# 51_24.net
KiCad netlist of a schematic drawn in Altium Designer
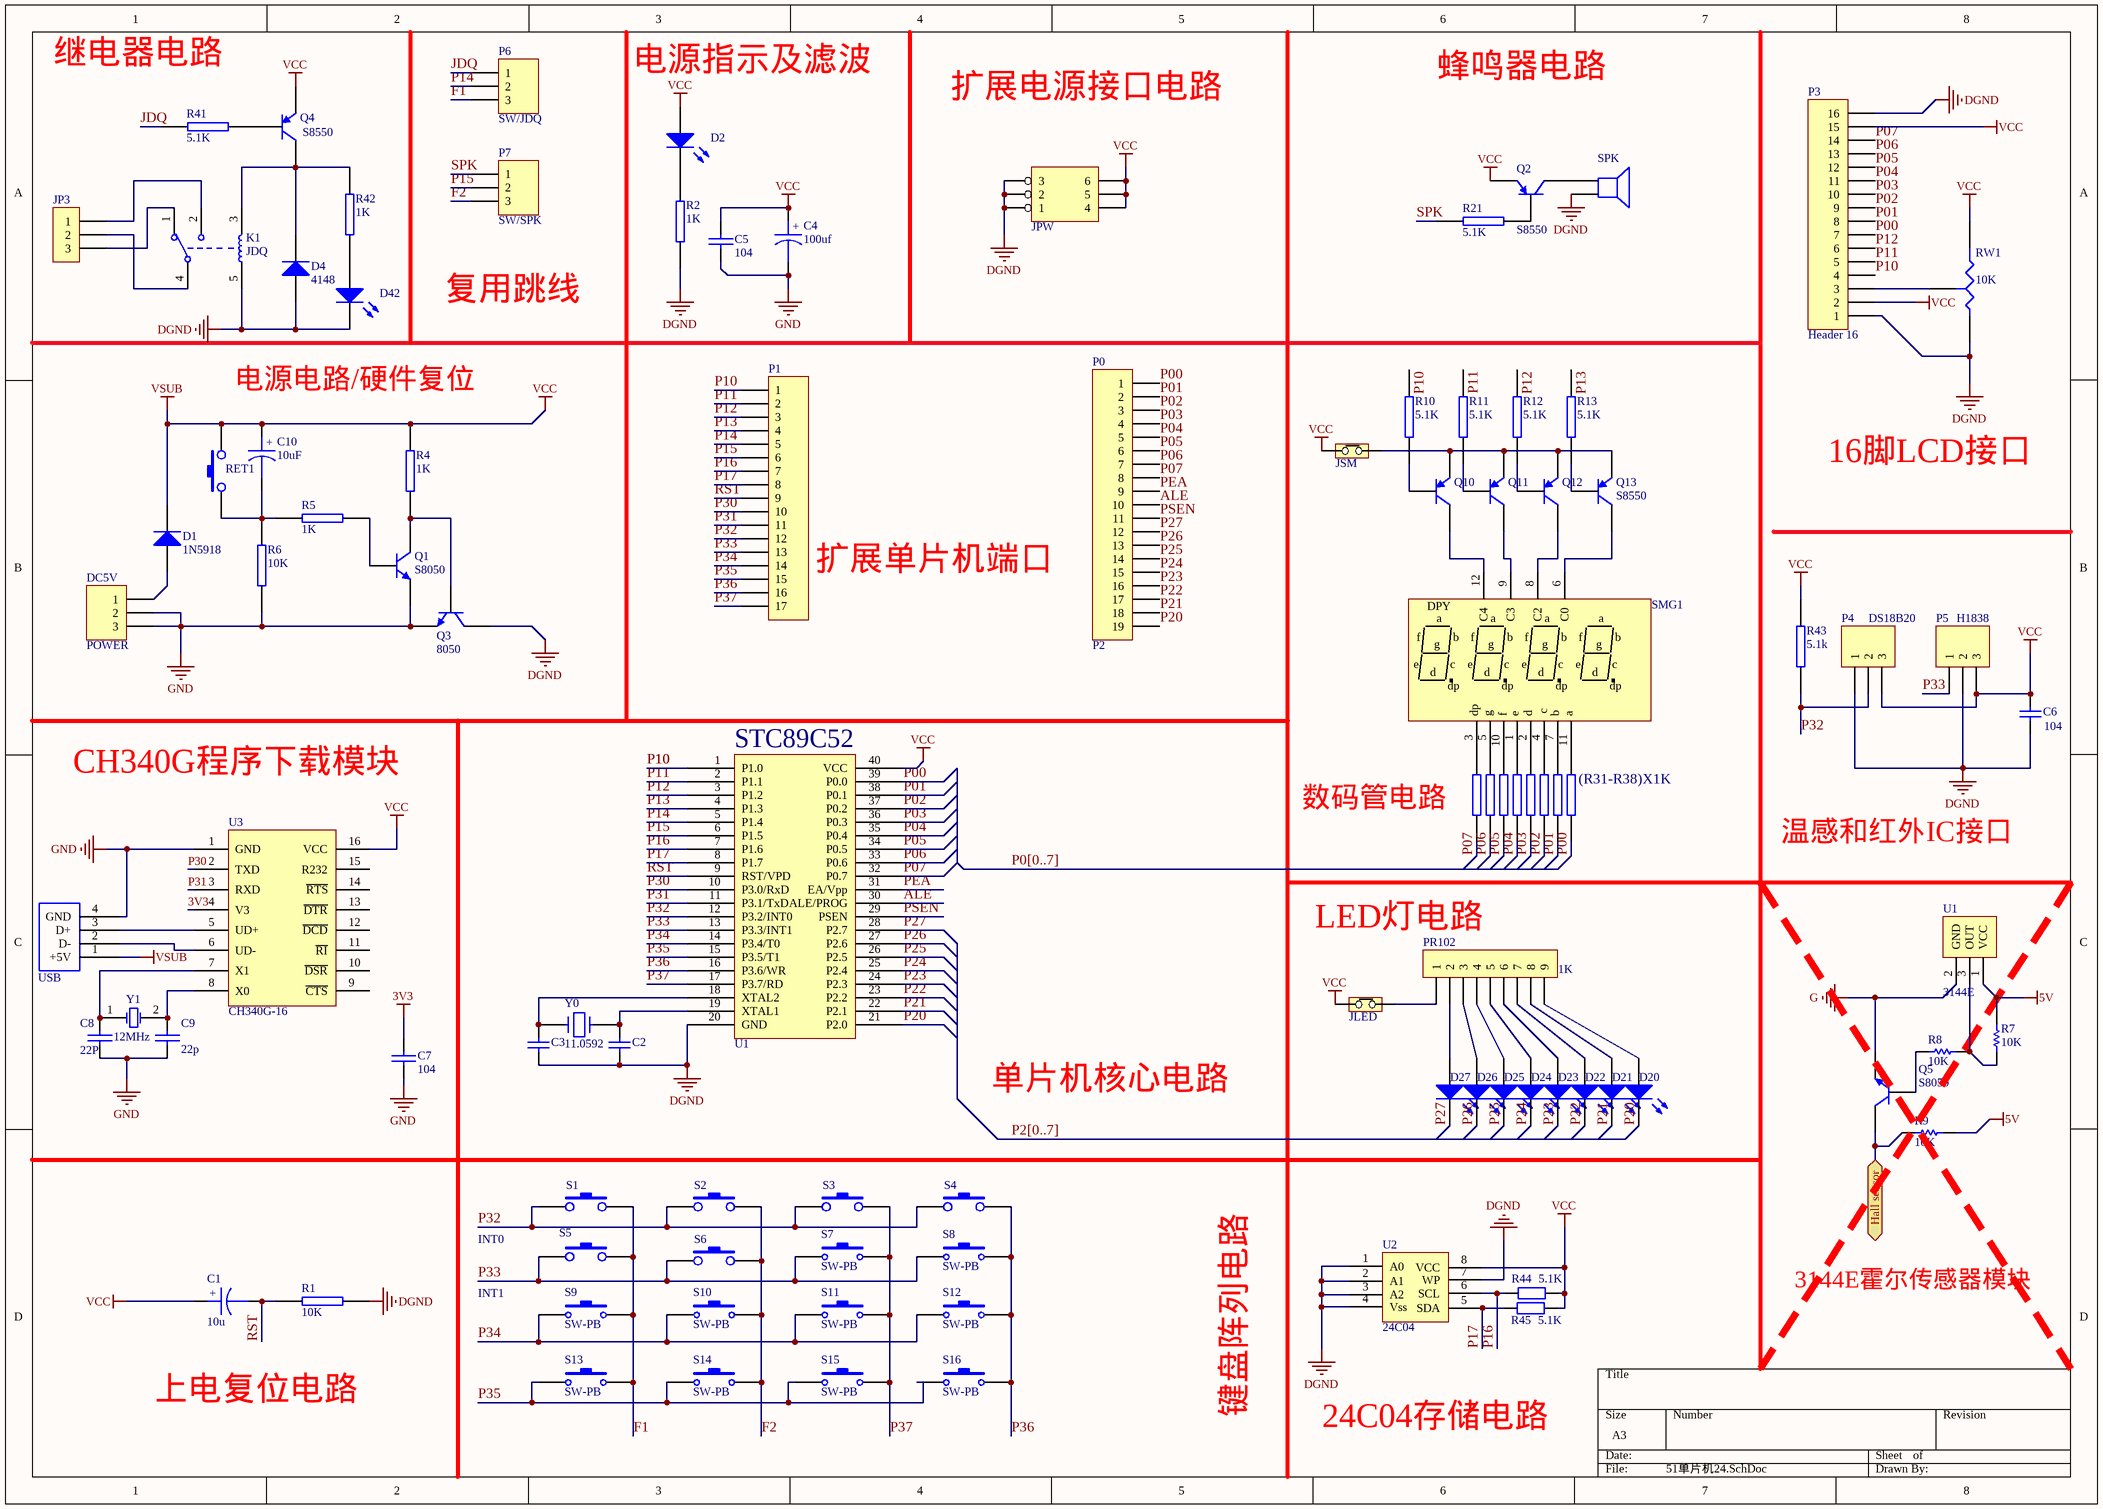
[diagram p0: 51单片机24.SchDoc]

(export (version "E")
  (design (tool "Eeschema 10.0.6"))
  (components
    (comp (ref "C1")
      (value "10u")
      (footprint "C2")
      (description "Capacitor")
      (libsource (lib "1") (part "CAPACITOR POL"))
    )
    (comp (ref "C2")
      (value "Cap")
      (footprint "RAD-0.1")
      (description "Capacitor")
      (fields
        (field (name "MANUFACTURER") "Generic Components")
        (field (name "PUBLISHER") "Altium Hobart Technology Centre")
      )
      (libsource (lib "Miscellaneous Devices") (part "Cap"))
    )
    (comp (ref "C3")
      (value "Cap")
      (footprint "RAD-0.1")
      (description "Capacitor")
      (fields
        (field (name "MANUFACTURER") "Generic Components")
        (field (name "PUBLISHER") "Altium Hobart Technology Centre")
      )
      (libsource (lib "Miscellaneous Devices") (part "Cap"))
    )
    (comp (ref "C4")
      (value "100uf")
      (footprint "c4")
      (description "Capacitor")
      (libsource (lib "1") (part "CAPACITOR POL"))
    )
    (comp (ref "C5")
      (value "104")
      (footprint "RAD-0.1")
      (description "Capacitor")
      (libsource (lib "1") (part "CAP"))
    )
    (comp (ref "C6")
      (value "104")
      (footprint "RAD-0.1")
      (description "Capacitor")
      (fields (field (name "Comment") "Cap") (field (name "PUBLISHER") "Altium Limited"))
      (libsource (lib "Miscellaneous Devices") (part "Cap"))
    )
    (comp (ref "C7")
      (value "104")
      (footprint "RAD-0.1")
      (description "Capacitor")
      (libsource (lib "Miscellaneous Devices") (part "CAP"))
    )
    (comp (ref "C8")
      (value "22P")
      (footprint "RAD-0.1")
      (description "Capacitor")
      (libsource (lib "Miscellaneous Devices") (part "CAP"))
    )
    (comp (ref "C9")
      (value "22p")
      (footprint "RAD-0.1")
      (description "Capacitor")
      (libsource (lib "Miscellaneous Devices") (part "CAP"))
    )
    (comp (ref "C10")
      (value "10uF")
      (footprint "c4")
      (description "Capacitor")
      (libsource (lib "1") (part "CAPACITOR POL"))
    )
    (comp (ref "D1")
      (value "1N5918")
      (footprint "4148")
      (description "3 Amp Medium Power Silicon Rectifier Diode")
      (fields (field (name "PUBLISHER") "Altium Limited"))
      (libsource (lib "Miscellaneous Devices") (part "Diode 1N5408"))
    )
    (comp (ref "D2")
      (value "LED0")
      (footprint "LED2")
      (description "Typical INFRARED GaAs LED")
      (fields (field (name "PUBLISHER") "Altium Limited"))
      (libsource (lib "Miscellaneous Devices") (part "LED0"))
    )
    (comp (ref "D4")
      (value "4148")
      (footprint "DO-41")
      (description "1 Amp General Purpose Rectifier")
      (fields (field (name "PUBLISHER") "Altium Limited"))
      (libsource (lib "Miscellaneous Devices") (part "Diode 1N4001"))
    )
    (comp (ref "D20")
      (value "LED0")
      (footprint "LED8")
      (description "Typical INFRARED GaAs LED")
      (fields (field (name "PUBLISHER") "Altium Limited"))
      (libsource (lib "Miscellaneous Devices") (part "LED0"))
    )
    (comp (ref "D21")
      (value "LED0")
      (footprint "LED8")
      (description "Typical INFRARED GaAs LED")
      (fields (field (name "PUBLISHER") "Altium Limited"))
      (libsource (lib "Miscellaneous Devices") (part "LED0"))
    )
    (comp (ref "D22")
      (value "LED0")
      (footprint "LED8")
      (description "Typical INFRARED GaAs LED")
      (fields (field (name "PUBLISHER") "Altium Limited"))
      (libsource (lib "Miscellaneous Devices") (part "LED0"))
    )
    (comp (ref "D23")
      (value "LED0")
      (footprint "LED8")
      (description "Typical INFRARED GaAs LED")
      (fields (field (name "PUBLISHER") "Altium Limited"))
      (libsource (lib "Miscellaneous Devices") (part "LED0"))
    )
    (comp (ref "D24")
      (value "LED0")
      (footprint "LED8")
      (description "Typical INFRARED GaAs LED")
      (fields (field (name "PUBLISHER") "Altium Limited"))
      (libsource (lib "Miscellaneous Devices") (part "LED0"))
    )
    (comp (ref "D25")
      (value "LED0")
      (footprint "LED8")
      (description "Typical INFRARED GaAs LED")
      (fields (field (name "PUBLISHER") "Altium Limited"))
      (libsource (lib "Miscellaneous Devices") (part "LED0"))
    )
    (comp (ref "D26")
      (value "LED0")
      (footprint "LED8")
      (description "Typical INFRARED GaAs LED")
      (fields (field (name "PUBLISHER") "Altium Limited"))
      (libsource (lib "Miscellaneous Devices") (part "LED0"))
    )
    (comp (ref "D27")
      (value "LED0")
      (footprint "LED8")
      (description "Typical INFRARED GaAs LED")
      (fields (field (name "PUBLISHER") "Altium Limited"))
      (libsource (lib "Miscellaneous Devices") (part "LED0"))
    )
    (comp (ref "D42")
      (value "LED0")
      (footprint "LED2")
      (description "Typical INFRARED GaAs LED")
      (fields (field (name "PUBLISHER") "Altium Limited"))
      (libsource (lib "Miscellaneous Devices") (part "LED0"))
    )
    (comp (ref "DC5V")
      (value "POWER")
      (footprint "DC5V-3")
      (description "Header, 3-Pin")
      (fields (field (name "PUBLISHER") "Altium Limited"))
      (libsource (lib "Miscellaneous Connectors") (part "Header 3"))
    )
    (comp (ref "JLED") (value "JJ") (footprint "j2") (libsource (lib "51单片机24_1") (part "JJ")))
    (comp (ref "JP3") (value "JP3") (footprint "JP3") (libsource (lib "51单片机24") (part "JP3")))
    (comp (ref "JPW") (value "JPW") (footprint "SIP") (libsource (lib "51单片机24_1") (part "JPW")))
    (comp (ref "JSM") (value "JJ") (footprint "j2") (libsource (lib "51单片机24_1") (part "JJ")))
    (comp (ref "K1") (value "JDQ") (footprint "JDQ") (libsource (lib "51单片机24_1") (part "JDQ")))
    (comp (ref "P0")
      (value "P2")
      (footprint "j19")
      (description "Header, 19-Pin")
      (fields (field (name "PUBLISHER") "Altium Limited"))
      (libsource (lib "单片机开发板") (part "Header 19"))
    )
    (comp (ref "P1")
      (value "Header 17")
      (footprint "j17")
      (description "Header, 17-Pin")
      (fields (field (name "PUBLISHER") "Altium Limited"))
      (libsource (lib "单片机开发板") (part "Header 17"))
    )
    (comp (ref "P3")
      (value "Header 16")
      (footprint "HDR1X16")
      (description "Header, 16-Pin")
      (fields (field (name "PUBLISHER") "Altium Limited"))
      (libsource (lib "Miscellaneous Connectors") (part "Header 16"))
    )
    (comp (ref "P4")
      (value "DS18B20")
      (footprint "HDR1X3")
      (description "Header, 3-Pin")
      (fields (field (name "PUBLISHER") "Altium Limited"))
      (libsource (lib "") (part "Header 3_2"))
    )
    (comp (ref "P5")
      (value "H1838")
      (footprint "HDR1X3")
      (description "Header, 3-Pin")
      (fields (field (name "PUBLISHER") "Altium Limited"))
      (libsource (lib "") (part "Header 3_2"))
    )
    (comp (ref "P6")
      (value "SW/JDQ")
      (footprint "HDR1X3")
      (description "Header, 3-Pin")
      (fields (field (name "PUBLISHER") "Altium Limited"))
      (libsource (lib "") (part "Header 3_1"))
    )
    (comp (ref "P7")
      (value "SW/SPK")
      (footprint "HDR1X3")
      (description "Header, 3-Pin")
      (fields (field (name "PUBLISHER") "Altium Limited"))
      (libsource (lib "") (part "Header 3_1"))
    )
    (comp (ref "PR102")
      (value "1K")
      (footprint "SIP-9")
      (description "Connector")
      (libsource (lib "1") (part "CON9"))
    )
    (comp (ref "Q1")
      (value "S8050")
      (footprint "sanjiguan")
      (description "NPN General Purpose Amplifier")
      (fields (field (name "PUBLISHER") "Altium Limited"))
      (libsource (lib "Miscellaneous Devices") (part "2N3904"))
    )
    (comp (ref "Q2")
      (value "S8550")
      (footprint "sanjiguan")
      (description "PNP General Purpose Amplifier")
      (fields (field (name "PUBLISHER") "Altium Limited"))
      (libsource (lib "Miscellaneous Devices") (part "2N3906"))
    )
    (comp (ref "Q3")
      (value "8050")
      (footprint "sanjiguan")
      (description "NPN General Purpose Amplifier")
      (fields (field (name "PUBLISHER") "Altium Limited"))
      (libsource (lib "Miscellaneous Devices") (part "2N3904"))
    )
    (comp (ref "Q4")
      (value "S8550")
      (footprint "sanjiguan")
      (description "PNP General Purpose Amplifier")
      (fields (field (name "PUBLISHER") "Altium Limited"))
      (libsource (lib "Miscellaneous Devices") (part "2N3906"))
    )
    (comp (ref "Q5")
      (value "S8050")
      (footprint "sanjiguan")
      (description "NPN General Purpose Amplifier")
      (fields (field (name "PUBLISHER") "Altium Limited"))
      (libsource (lib "Miscellaneous Devices") (part "2N3904"))
    )
    (comp (ref "Q10")
      (value "S8550")
      (footprint "sanjiguan")
      (description "PNP General Purpose Amplifier")
      (fields (field (name "PUBLISHER") "Altium Limited"))
      (libsource (lib "Miscellaneous Devices") (part "2N3906"))
    )
    (comp (ref "Q11")
      (value "S8550")
      (footprint "sanjiguan")
      (description "PNP General Purpose Amplifier")
      (fields (field (name "PUBLISHER") "Altium Limited"))
      (libsource (lib "Miscellaneous Devices") (part "2N3906"))
    )
    (comp (ref "Q12")
      (value "S8550")
      (footprint "sanjiguan")
      (description "PNP General Purpose Amplifier")
      (fields (field (name "PUBLISHER") "Altium Limited"))
      (libsource (lib "Miscellaneous Devices") (part "2N3906"))
    )
    (comp (ref "Q13")
      (value "S8550")
      (footprint "sanjiguan")
      (description "PNP General Purpose Amplifier")
      (fields (field (name "PUBLISHER") "Altium Limited"))
      (libsource (lib "Miscellaneous Devices") (part "2N3906"))
    )
    (comp (ref "R1")
      (value "10K")
      (footprint "axial0.4")
      (libsource (lib "Miscellaneous Devices") (part "RES2"))
    )
    (comp (ref "R2") (value "1K") (footprint "axial0.4") (libsource (lib "1") (part "RES2")))
    (comp (ref "R4")
      (value "1K")
      (footprint "axial0.4")
      (libsource (lib "Miscellaneous Devices") (part "RES2"))
    )
    (comp (ref "R5")
      (value "1K")
      (footprint "axial0.4")
      (libsource (lib "Miscellaneous Devices") (part "RES2"))
    )
    (comp (ref "R6")
      (value "10K")
      (footprint "axial0.4")
      (libsource (lib "Miscellaneous Devices") (part "RES2"))
    )
    (comp (ref "R7")
      (value "10K")
      (footprint "AXIAL-0.3")
      (description "Resistor")
      (fields (field (name "Comment") "Res1") (field (name "PUBLISHER") "Altium Limited"))
      (libsource (lib "Miscellaneous Devices") (part "Res1"))
    )
    (comp (ref "R8")
      (value "10K")
      (footprint "AXIAL-0.3")
      (description "Resistor")
      (fields (field (name "Comment") "Res1") (field (name "PUBLISHER") "Altium Limited"))
      (libsource (lib "Miscellaneous Devices") (part "Res1"))
    )
    (comp (ref "R9")
      (value "10K")
      (footprint "AXIAL-0.3")
      (description "Resistor")
      (fields (field (name "Comment") "Res1") (field (name "PUBLISHER") "Altium Limited"))
      (libsource (lib "Miscellaneous Devices") (part "Res1"))
    )
    (comp (ref "R10")
      (value "5.1K")
      (footprint "axial0.4")
      (libsource (lib "Miscellaneous Devices") (part "RES2"))
    )
    (comp (ref "R11")
      (value "5.1K")
      (footprint "axial0.4")
      (libsource (lib "Miscellaneous Devices") (part "RES2"))
    )
    (comp (ref "R12")
      (value "5.1K")
      (footprint "axial0.4")
      (libsource (lib "Miscellaneous Devices") (part "RES2"))
    )
    (comp (ref "R13")
      (value "5.1K")
      (footprint "axial0.4")
      (libsource (lib "Miscellaneous Devices") (part "RES2"))
    )
    (comp (ref "R21")
      (value "5.1K")
      (footprint "axial0.4")
      (libsource (lib "Miscellaneous Devices") (part "RES2"))
    )
    (comp (ref "R31")
      (value "1K")
      (footprint "axial0.4")
      (libsource (lib "Miscellaneous Devices") (part "RES2"))
    )
    (comp (ref "R32")
      (value "1K")
      (footprint "axial0.4")
      (libsource (lib "Miscellaneous Devices") (part "RES2"))
    )
    (comp (ref "R33")
      (value "1K")
      (footprint "axial0.4")
      (libsource (lib "Miscellaneous Devices") (part "RES2"))
    )
    (comp (ref "R34")
      (value "1K")
      (footprint "axial0.4")
      (libsource (lib "Miscellaneous Devices") (part "RES2"))
    )
    (comp (ref "R35")
      (value "1K")
      (footprint "axial0.4")
      (libsource (lib "Miscellaneous Devices") (part "RES2"))
    )
    (comp (ref "R36")
      (value "1K")
      (footprint "axial0.4")
      (libsource (lib "Miscellaneous Devices") (part "RES2"))
    )
    (comp (ref "R37")
      (value "1K")
      (footprint "axial0.4")
      (libsource (lib "Miscellaneous Devices") (part "RES2"))
    )
    (comp (ref "R38")
      (value "1K")
      (footprint "axial0.4")
      (libsource (lib "Miscellaneous Devices") (part "RES2"))
    )
    (comp (ref "R41")
      (value "5.1K")
      (footprint "axial0.4")
      (libsource (lib "Miscellaneous Devices") (part "RES2"))
    )
    (comp (ref "R42")
      (value "1K")
      (footprint "axial0.4")
      (libsource (lib "Miscellaneous Devices") (part "RES2"))
    )
    (comp (ref "R43")
      (value "5.1k")
      (footprint "axial0.4")
      (libsource (lib "Miscellaneous Devices") (part "RES2"))
    )
    (comp (ref "R44")
      (value "5.1K")
      (footprint "AXIAL-0.4")
      (description "Resistor")
      (fields (field (name "PUBLISHER") "Altium Limited"))
      (libsource (lib "Miscellaneous Devices") (part "Res2"))
    )
    (comp (ref "R45")
      (value "5.1K")
      (footprint "AXIAL-0.4")
      (description "Resistor")
      (fields (field (name "PUBLISHER") "Altium Limited"))
      (libsource (lib "Miscellaneous Devices") (part "Res2"))
    )
    (comp (ref "RET1")
      (value "RET")
      (footprint "sw")
      (libsource (lib "Miscellaneous Devices") (part "SW-PB"))
    )
    (comp (ref "RW1")
      (value "10K")
      (footprint "RW")
      (description "Tapped Resistor")
      (fields (field (name "Comment") "Res Tap") (field (name "PUBLISHER") "Altium Limited"))
      (libsource (lib "Miscellaneous Devices") (part "Res Tap"))
    )
    (comp (ref "S1") (value "RET") (footprint "sw") (libsource (lib "Miscellaneous Devices") (part "SW-PB")))
    (comp (ref "S2") (value "RET") (footprint "sw") (libsource (lib "Miscellaneous Devices") (part "SW-PB")))
    (comp (ref "S3") (value "RET") (footprint "sw") (libsource (lib "Miscellaneous Devices") (part "SW-PB")))
    (comp (ref "S4") (value "RET") (footprint "sw") (libsource (lib "Miscellaneous Devices") (part "SW-PB")))
    (comp (ref "S5") (value "RET") (footprint "sw") (libsource (lib "Miscellaneous Devices") (part "SW-PB")))
    (comp (ref "S6") (value "RET") (footprint "sw") (libsource (lib "Miscellaneous Devices") (part "SW-PB")))
    (comp (ref "S7")
      (value "SW-PB")
      (footprint "SW")
      (description "Switch")
      (fields (field (name "PUBLISHER") "Altium Limited"))
      (libsource (lib "") (part "SW-PB_1"))
    )
    (comp (ref "S8")
      (value "SW-PB")
      (footprint "SW")
      (description "Switch")
      (fields (field (name "PUBLISHER") "Altium Limited"))
      (libsource (lib "") (part "SW-PB_1"))
    )
    (comp (ref "S9")
      (value "SW-PB")
      (footprint "SW")
      (description "Switch")
      (fields (field (name "PUBLISHER") "Altium Limited"))
      (libsource (lib "") (part "SW-PB_1"))
    )
    (comp (ref "S10")
      (value "SW-PB")
      (footprint "SW")
      (description "Switch")
      (fields (field (name "PUBLISHER") "Altium Limited"))
      (libsource (lib "") (part "SW-PB_1"))
    )
    (comp (ref "S11")
      (value "SW-PB")
      (footprint "SW")
      (description "Switch")
      (fields (field (name "PUBLISHER") "Altium Limited"))
      (libsource (lib "") (part "SW-PB_1"))
    )
    (comp (ref "S12")
      (value "SW-PB")
      (footprint "SW")
      (description "Switch")
      (fields (field (name "PUBLISHER") "Altium Limited"))
      (libsource (lib "") (part "SW-PB_1"))
    )
    (comp (ref "S13")
      (value "SW-PB")
      (footprint "SW")
      (description "Switch")
      (fields (field (name "PUBLISHER") "Altium Limited"))
      (libsource (lib "") (part "SW-PB_1"))
    )
    (comp (ref "S14")
      (value "SW-PB")
      (footprint "SW")
      (description "Switch")
      (fields (field (name "PUBLISHER") "Altium Limited"))
      (libsource (lib "") (part "SW-PB_1"))
    )
    (comp (ref "S15")
      (value "SW-PB")
      (footprint "SW")
      (description "Switch")
      (fields (field (name "PUBLISHER") "Altium Limited"))
      (libsource (lib "") (part "SW-PB_1"))
    )
    (comp (ref "S16")
      (value "SW-PB")
      (footprint "SW")
      (description "Switch")
      (fields (field (name "PUBLISHER") "Altium Limited"))
      (libsource (lib "") (part "SW-PB_1"))
    )
    (comp (ref "SMG1") (value "SMG") (footprint "smg") (libsource (lib "51单片机24") (part "SMG")))
    (comp (ref "SPK")
      (value "Speaker")
      (footprint "HDR1X4")
      (libsource (lib "Miscellaneous Devices") (part "SPEAKER"))
    )
    (comp (ref "STC89C52") (value "U1") (footprint "S52") (libsource (lib "51单片机24_1") (part "89C51")))
    (comp (ref "U1")
      (value "3144E")
      (footprint "HDR1X3")
      (description "开关式霍尔传感器")
      (libsource (lib "PCB-Design-of-the-8051") (part "3144E"))
    )
    (comp (ref "U2") (value "24C04") (footprint "DIP8") (libsource (lib "51单片机24_1") (part "24C04")))
    (comp (ref "U3")
      (value "CH340G-16")
      (footprint "SOP-16 - duplicate")
      (libsource (lib "51单片机24_1") (part "CH340G-16"))
    )
    (comp (ref "USB")
      (value "CON4")
      (footprint "USB")
      (description "Connector")
      (libsource (lib "1") (part "CON4"))
    )
    (comp (ref "Y0")
      (value "11.0592")
      (footprint "XTAL1")
      (description "Crystal")
      (libsource (lib "1") (part "CRYSTAL"))
    )
    (comp (ref "Y1")
      (value "12MHz")
      (footprint "XTAL1")
      (description "Crystal Oscillator")
      (fields (field (name "PUBLISHER") "Altium Limited"))
      (libsource (lib "Miscellaneous Devices") (part "XTAL"))
    )
  )
  (nets
    (net (code "1") (name "/ALE") (class "Default")
      (node (ref "P0") (pin "10") (pinfunction "10_10") (pintype "passive"))
      (node (ref "STC89C52") (pin "30") (pinfunction "ALE/PROG_30") (pintype "passive"))
    )
    (net (code "2") (name "/F1") (class "Default")
      (node (ref "P6") (pin "3") (pinfunction "3_3") (pintype "passive"))
      (node (ref "S1") (pin "2") (pinfunction "2_2") (pintype "passive"))
      (node (ref "S13") (pin "2") (pinfunction "2_2") (pintype "passive"))
      (node (ref "S5") (pin "2") (pinfunction "2_2") (pintype "passive"))
      (node (ref "S9") (pin "2") (pinfunction "2_2") (pintype "passive"))
    )
    (net (code "3") (name "/F2") (class "Default")
      (node (ref "P7") (pin "3") (pinfunction "3_3") (pintype "passive"))
      (node (ref "S10") (pin "2") (pinfunction "2_2") (pintype "passive"))
      (node (ref "S14") (pin "2") (pinfunction "2_2") (pintype "passive"))
      (node (ref "S2") (pin "2") (pinfunction "2_2") (pintype "passive"))
      (node (ref "S6") (pin "2") (pinfunction "2_2") (pintype "passive"))
    )
    (net (code "4") (name "/Hall sensor") (class "Default")
      (node (ref "Q5") (pin "3") (pinfunction "C_3") (pintype "passive"))
      (node (ref "R9") (pin "1") (pinfunction "1_1") (pintype "passive"))
    )
    (net (code "5") (name "/JDQ") (class "Default")
      (node (ref "P6") (pin "1") (pinfunction "1_1") (pintype "passive"))
      (node (ref "R41") (pin "1") (pinfunction "1_1") (pintype "passive"))
    )
    (net (code "6") (name "/P00") (class "Default")
      (node (ref "P0") (pin "1") (pinfunction "1_1") (pintype "passive"))
      (node (ref "P3") (pin "7") (pinfunction "7_7") (pintype "passive"))
      (node (ref "R31") (pin "1") (pinfunction "1_1") (pintype "passive"))
      (node (ref "STC89C52") (pin "39") (pinfunction "P0.0_39") (pintype "passive"))
    )
    (net (code "8") (name "/P01") (class "Default")
      (node (ref "P0") (pin "2") (pinfunction "2_2") (pintype "passive"))
      (node (ref "P3") (pin "8") (pinfunction "8_8") (pintype "passive"))
      (node (ref "R32") (pin "1") (pinfunction "1_1") (pintype "passive"))
      (node (ref "STC89C52") (pin "38") (pinfunction "P0.1_38") (pintype "passive"))
    )
    (net (code "9") (name "/P02") (class "Default")
      (node (ref "P0") (pin "3") (pinfunction "3_3") (pintype "passive"))
      (node (ref "P3") (pin "9") (pinfunction "9_9") (pintype "passive"))
      (node (ref "R33") (pin "1") (pinfunction "1_1") (pintype "passive"))
      (node (ref "STC89C52") (pin "37") (pinfunction "P0.2_37") (pintype "passive"))
    )
    (net (code "11") (name "/P03") (class "Default")
      (node (ref "P0") (pin "4") (pinfunction "4_4") (pintype "passive"))
      (node (ref "P3") (pin "10") (pinfunction "10_10") (pintype "passive"))
      (node (ref "R34") (pin "1") (pinfunction "1_1") (pintype "passive"))
      (node (ref "STC89C52") (pin "36") (pinfunction "P0.3_36") (pintype "passive"))
    )
    (net (code "12") (name "/P04") (class "Default")
      (node (ref "P0") (pin "5") (pinfunction "5_5") (pintype "passive"))
      (node (ref "P3") (pin "11") (pinfunction "11_11") (pintype "passive"))
      (node (ref "R35") (pin "1") (pinfunction "1_1") (pintype "passive"))
      (node (ref "STC89C52") (pin "35") (pinfunction "P0.4_35") (pintype "passive"))
    )
    (net (code "13") (name "/P05") (class "Default")
      (node (ref "P0") (pin "6") (pinfunction "6_6") (pintype "passive"))
      (node (ref "P3") (pin "12") (pinfunction "12_12") (pintype "passive"))
      (node (ref "R36") (pin "1") (pinfunction "1_1") (pintype "passive"))
      (node (ref "STC89C52") (pin "34") (pinfunction "P0.5_34") (pintype "passive"))
    )
    (net (code "14") (name "/P06") (class "Default")
      (node (ref "P0") (pin "7") (pinfunction "7_7") (pintype "passive"))
      (node (ref "P3") (pin "13") (pinfunction "13_13") (pintype "passive"))
      (node (ref "R37") (pin "1") (pinfunction "1_1") (pintype "passive"))
      (node (ref "STC89C52") (pin "33") (pinfunction "P0.6_33") (pintype "passive"))
    )
    (net (code "15") (name "/P07") (class "Default")
      (node (ref "P0") (pin "8") (pinfunction "8_8") (pintype "passive"))
      (node (ref "P3") (pin "14") (pinfunction "14_14") (pintype "passive"))
      (node (ref "R38") (pin "1") (pinfunction "1_1") (pintype "passive"))
      (node (ref "STC89C52") (pin "32") (pinfunction "P0.7_32") (pintype "passive"))
    )
    (net (code "16") (name "/P10") (class "Default")
      (node (ref "P1") (pin "1") (pinfunction "1_1") (pintype "passive"))
      (node (ref "P3") (pin "4") (pinfunction "4_4") (pintype "passive"))
      (node (ref "R10") (pin "2") (pinfunction "2_2") (pintype "passive"))
      (node (ref "STC89C52") (pin "1") (pinfunction "P1.0_1") (pintype "passive"))
    )
    (net (code "17") (name "/P11") (class "Default")
      (node (ref "P1") (pin "2") (pinfunction "2_2") (pintype "passive"))
      (node (ref "P3") (pin "5") (pinfunction "5_5") (pintype "passive"))
      (node (ref "R11") (pin "2") (pinfunction "2_2") (pintype "passive"))
      (node (ref "STC89C52") (pin "2") (pinfunction "P1.1_2") (pintype "passive"))
    )
    (net (code "18") (name "/P12") (class "Default")
      (node (ref "P1") (pin "3") (pinfunction "3_3") (pintype "passive"))
      (node (ref "P3") (pin "6") (pinfunction "6_6") (pintype "passive"))
      (node (ref "R12") (pin "2") (pinfunction "2_2") (pintype "passive"))
      (node (ref "STC89C52") (pin "3") (pinfunction "P1.2_3") (pintype "passive"))
    )
    (net (code "19") (name "/P13") (class "Default")
      (node (ref "P1") (pin "4") (pinfunction "4_4") (pintype "passive"))
      (node (ref "R13") (pin "2") (pinfunction "2_2") (pintype "passive"))
      (node (ref "STC89C52") (pin "4") (pinfunction "P1.3_4") (pintype "passive"))
    )
    (net (code "20") (name "/P14") (class "Default")
      (node (ref "P1") (pin "5") (pinfunction "5_5") (pintype "passive"))
      (node (ref "P6") (pin "2") (pinfunction "2_2") (pintype "passive"))
      (node (ref "STC89C52") (pin "5") (pinfunction "P1.4_5") (pintype "passive"))
    )
    (net (code "21") (name "/P15") (class "Default")
      (node (ref "P1") (pin "6") (pinfunction "6_6") (pintype "passive"))
      (node (ref "P7") (pin "2") (pinfunction "2_2") (pintype "passive"))
      (node (ref "STC89C52") (pin "6") (pinfunction "P1.5_6") (pintype "passive"))
    )
    (net (code "22") (name "/P16") (class "Default")
      (node (ref "P1") (pin "7") (pinfunction "7_7") (pintype "passive"))
      (node (ref "R44") (pin "1") (pinfunction "1_1") (pintype "passive"))
      (node (ref "STC89C52") (pin "7") (pinfunction "P1.6_7") (pintype "passive"))
      (node (ref "U2") (pin "6") (pinfunction "SCL_6") (pintype "passive"))
    )
    (net (code "23") (name "/P17") (class "Default")
      (node (ref "P1") (pin "8") (pinfunction "8_8") (pintype "passive"))
      (node (ref "R45") (pin "1") (pinfunction "1_1") (pintype "passive"))
      (node (ref "STC89C52") (pin "8") (pinfunction "P1.7_8") (pintype "passive"))
      (node (ref "U2") (pin "5") (pinfunction "SDA_5") (pintype "passive"))
    )
    (net (code "24") (name "/P20") (class "Default")
      (node (ref "D20") (pin "2") (pinfunction "K_2") (pintype "passive"))
      (node (ref "P0") (pin "19") (pinfunction "19_19") (pintype "passive"))
      (node (ref "STC89C52") (pin "21") (pinfunction "P2.0_21") (pintype "passive"))
    )
    (net (code "25") (name "/P21") (class "Default")
      (node (ref "D21") (pin "2") (pinfunction "K_2") (pintype "passive"))
      (node (ref "P0") (pin "18") (pinfunction "18_18") (pintype "passive"))
      (node (ref "STC89C52") (pin "22") (pinfunction "P2.1_22") (pintype "passive"))
    )
    (net (code "26") (name "/P22") (class "Default")
      (node (ref "D22") (pin "2") (pinfunction "K_2") (pintype "passive"))
      (node (ref "P0") (pin "17") (pinfunction "17_17") (pintype "passive"))
      (node (ref "STC89C52") (pin "23") (pinfunction "P2.2_23") (pintype "passive"))
    )
    (net (code "27") (name "/P23") (class "Default")
      (node (ref "D23") (pin "2") (pinfunction "K_2") (pintype "passive"))
      (node (ref "P0") (pin "16") (pinfunction "16_16") (pintype "passive"))
      (node (ref "STC89C52") (pin "24") (pinfunction "P2.3_24") (pintype "passive"))
    )
    (net (code "28") (name "/P24") (class "Default")
      (node (ref "D24") (pin "2") (pinfunction "K_2") (pintype "passive"))
      (node (ref "P0") (pin "15") (pinfunction "15_15") (pintype "passive"))
      (node (ref "STC89C52") (pin "25") (pinfunction "P2.4_25") (pintype "passive"))
    )
    (net (code "29") (name "/P25") (class "Default")
      (node (ref "D25") (pin "2") (pinfunction "K_2") (pintype "passive"))
      (node (ref "P0") (pin "14") (pinfunction "14_14") (pintype "passive"))
      (node (ref "STC89C52") (pin "26") (pinfunction "P2.5_26") (pintype "passive"))
    )
    (net (code "30") (name "/P26") (class "Default")
      (node (ref "D26") (pin "2") (pinfunction "K_2") (pintype "passive"))
      (node (ref "P0") (pin "13") (pinfunction "13_13") (pintype "passive"))
      (node (ref "STC89C52") (pin "27") (pinfunction "P2.6_27") (pintype "passive"))
    )
    (net (code "31") (name "/P27") (class "Default")
      (node (ref "D27") (pin "2") (pinfunction "K_2") (pintype "passive"))
      (node (ref "P0") (pin "12") (pinfunction "12_12") (pintype "passive"))
      (node (ref "STC89C52") (pin "28") (pinfunction "P2.7_28") (pintype "passive"))
    )
    (net (code "32") (name "/P30") (class "Default")
      (node (ref "P1") (pin "10") (pinfunction "10_10") (pintype "passive"))
      (node (ref "STC89C52") (pin "10") (pinfunction "P3.0/RxD_10") (pintype "passive"))
      (node (ref "U3") (pin "2") (pinfunction "TXD_2") (pintype "passive"))
    )
    (net (code "33") (name "/P31") (class "Default")
      (node (ref "P1") (pin "11") (pinfunction "11_11") (pintype "passive"))
      (node (ref "STC89C52") (pin "11") (pinfunction "P3.1/TxD_11") (pintype "passive"))
      (node (ref "U3") (pin "3") (pinfunction "RXD_3") (pintype "passive"))
    )
    (net (code "34") (name "/P32") (class "Default")
      (node (ref "P1") (pin "12") (pinfunction "12_12") (pintype "passive"))
      (node (ref "P4") (pin "2") (pinfunction "2_2") (pintype "passive"))
      (node (ref "R43") (pin "1") (pinfunction "1_1") (pintype "passive"))
      (node (ref "S1") (pin "1") (pinfunction "1_1") (pintype "passive"))
      (node (ref "S2") (pin "1") (pinfunction "1_1") (pintype "passive"))
      (node (ref "S3") (pin "1") (pinfunction "1_1") (pintype "passive"))
      (node (ref "S4") (pin "1") (pinfunction "1_1") (pintype "passive"))
      (node (ref "STC89C52") (pin "12") (pinfunction "P3.2/INT0_12") (pintype "passive"))
    )
    (net (code "35") (name "/P33") (class "Default")
      (node (ref "P1") (pin "13") (pinfunction "13_13") (pintype "passive"))
      (node (ref "P5") (pin "1") (pinfunction "1_1") (pintype "passive"))
      (node (ref "S5") (pin "1") (pinfunction "1_1") (pintype "passive"))
      (node (ref "S6") (pin "1") (pinfunction "1_1") (pintype "passive"))
      (node (ref "S7") (pin "1") (pinfunction "1_1") (pintype "passive"))
      (node (ref "S8") (pin "1") (pinfunction "1_1") (pintype "passive"))
      (node (ref "STC89C52") (pin "13") (pinfunction "P3.3/INT1_13") (pintype "passive"))
    )
    (net (code "36") (name "/P34") (class "Default")
      (node (ref "P1") (pin "14") (pinfunction "14_14") (pintype "passive"))
      (node (ref "S10") (pin "1") (pinfunction "1_1") (pintype "passive"))
      (node (ref "S11") (pin "1") (pinfunction "1_1") (pintype "passive"))
      (node (ref "S12") (pin "1") (pinfunction "1_1") (pintype "passive"))
      (node (ref "S9") (pin "1") (pinfunction "1_1") (pintype "passive"))
      (node (ref "STC89C52") (pin "14") (pinfunction "P3.4/T0_14") (pintype "passive"))
    )
    (net (code "37") (name "/P35") (class "Default")
      (node (ref "P1") (pin "15") (pinfunction "15_15") (pintype "passive"))
      (node (ref "S13") (pin "1") (pinfunction "1_1") (pintype "passive"))
      (node (ref "S14") (pin "1") (pinfunction "1_1") (pintype "passive"))
      (node (ref "S15") (pin "1") (pinfunction "1_1") (pintype "passive"))
      (node (ref "S16") (pin "1") (pinfunction "1_1") (pintype "passive"))
      (node (ref "STC89C52") (pin "15") (pinfunction "P3.5/T1_15") (pintype "passive"))
    )
    (net (code "38") (name "/P36") (class "Default")
      (node (ref "P1") (pin "16") (pinfunction "16_16") (pintype "passive"))
      (node (ref "S12") (pin "2") (pinfunction "2_2") (pintype "passive"))
      (node (ref "S16") (pin "2") (pinfunction "2_2") (pintype "passive"))
      (node (ref "S4") (pin "2") (pinfunction "2_2") (pintype "passive"))
      (node (ref "S8") (pin "2") (pinfunction "2_2") (pintype "passive"))
      (node (ref "STC89C52") (pin "16") (pinfunction "P3.6/WR_16") (pintype "passive"))
    )
    (net (code "39") (name "/P37") (class "Default")
      (node (ref "P1") (pin "17") (pinfunction "17_17") (pintype "passive"))
      (node (ref "S11") (pin "2") (pinfunction "2_2") (pintype "passive"))
      (node (ref "S15") (pin "2") (pinfunction "2_2") (pintype "passive"))
      (node (ref "S3") (pin "2") (pinfunction "2_2") (pintype "passive"))
      (node (ref "S7") (pin "2") (pinfunction "2_2") (pintype "passive"))
      (node (ref "STC89C52") (pin "17") (pinfunction "P3.7/RD_17") (pintype "passive"))
    )
    (net (code "40") (name "/PEA") (class "Default")
      (node (ref "P0") (pin "9") (pinfunction "9_9") (pintype "passive"))
      (node (ref "STC89C52") (pin "31") (pinfunction "EA/Vpp_31") (pintype "passive"))
    )
    (net (code "41") (name "/PSEN") (class "Default")
      (node (ref "P0") (pin "11") (pinfunction "11_11") (pintype "passive"))
      (node (ref "STC89C52") (pin "29") (pinfunction "PSEN_29") (pintype "passive"))
    )
    (net (code "42") (name "/RST") (class "Default")
      (node (ref "C1") (pin "2") (pinfunction "2_2") (pintype "passive"))
      (node (ref "P1") (pin "9") (pinfunction "9_9") (pintype "passive"))
      (node (ref "R1") (pin "2") (pinfunction "2_2") (pintype "passive"))
      (node (ref "STC89C52") (pin "9") (pinfunction "RST/VPD_9") (pintype "passive"))
    )
    (net (code "43") (name "/SPK") (class "Default")
      (node (ref "P7") (pin "1") (pinfunction "1_1") (pintype "passive"))
      (node (ref "R21") (pin "1") (pinfunction "1_1") (pintype "passive"))
    )
    (net (code "44") (name "3V3") (class "Default")
      (node (ref "C7") (pin "1") (pinfunction "1_1") (pintype "passive"))
      (node (ref "U3") (pin "4") (pinfunction "V3_4") (pintype "passive"))
    )
    (net (code "45") (name "5V") (class "Default")
      (node (ref "R7") (pin "2") (pinfunction "2_2") (pintype "passive"))
      (node (ref "R9") (pin "2") (pinfunction "2_2") (pintype "passive"))
      (node (ref "U1") (pin "1") (pinfunction "VCC_1") (pintype "passive"))
    )
    (net (code "46") (name "DGND") (class "Default")
      (node (ref "C2") (pin "1") (pinfunction "1_1") (pintype "passive"))
      (node (ref "C3") (pin "1") (pinfunction "1_1") (pintype "passive"))
      (node (ref "C6") (pin "1") (pinfunction "1_1") (pintype "passive"))
      (node (ref "D4") (pin "1") (pinfunction "A_1") (pintype "passive"))
      (node (ref "D42") (pin "2") (pinfunction "K_2") (pintype "passive"))
      (node (ref "JPW") (pin "1") (pinfunction "1_1") (pintype "passive"))
      (node (ref "JPW") (pin "2") (pinfunction "2_2") (pintype "passive"))
      (node (ref "JPW") (pin "3") (pinfunction "3_3") (pintype "passive"))
      (node (ref "K1") (pin "5") (pinfunction "5_5") (pintype "passive"))
      (node (ref "P3") (pin "1") (pinfunction "1_1") (pintype "passive"))
      (node (ref "P3") (pin "16") (pinfunction "16_16") (pintype "passive"))
      (node (ref "P4") (pin "1") (pinfunction "1_1") (pintype "passive"))
      (node (ref "P5") (pin "2") (pinfunction "2_2") (pintype "passive"))
      (node (ref "Q3") (pin "3") (pinfunction "C_3") (pintype "passive"))
      (node (ref "R1") (pin "1") (pinfunction "1_1") (pintype "passive"))
      (node (ref "R2") (pin "1") (pinfunction "1_1") (pintype "passive"))
      (node (ref "RW1") (pin "1") (pinfunction "A_1") (pintype "passive"))
      (node (ref "SPK") (pin "2") (pinfunction "K_2") (pintype "passive"))
      (node (ref "STC89C52") (pin "20") (pinfunction "GND_20") (pintype "passive"))
      (node (ref "U2") (pin "1") (pinfunction "A0_1") (pintype "passive"))
      (node (ref "U2") (pin "2") (pinfunction "A1_2") (pintype "passive"))
      (node (ref "U2") (pin "3") (pinfunction "A2_3") (pintype "passive"))
      (node (ref "U2") (pin "4") (pinfunction "Vss_4") (pintype "passive"))
      (node (ref "U2") (pin "7") (pinfunction "WP_7") (pintype "passive"))
    )
    (net (code "47") (name "G") (class "Default")
      (node (ref "Q5") (pin "1") (pinfunction "E_1") (pintype "passive"))
      (node (ref "U1") (pin "2") (pinfunction "GND_2") (pintype "passive"))
    )
    (net (code "48") (name "GND") (class "Default")
      (node (ref "C4") (pin "2") (pinfunction "2_2") (pintype "passive"))
      (node (ref "C5") (pin "2") (pinfunction "2_2") (pintype "passive"))
      (node (ref "C7") (pin "2") (pinfunction "2_2") (pintype "passive"))
      (node (ref "C8") (pin "2") (pinfunction "2_2") (pintype "passive"))
      (node (ref "C9") (pin "2") (pinfunction "2_2") (pintype "passive"))
      (node (ref "DC5V") (pin "2") (pinfunction "2_2") (pintype "passive"))
      (node (ref "DC5V") (pin "3") (pinfunction "3_3") (pintype "passive"))
      (node (ref "Q1") (pin "1") (pinfunction "E_1") (pintype "passive"))
      (node (ref "Q3") (pin "1") (pinfunction "E_1") (pintype "passive"))
      (node (ref "R6") (pin "2") (pinfunction "2_2") (pintype "passive"))
      (node (ref "U3") (pin "1") (pinfunction "GND_1") (pintype "passive"))
      (node (ref "USB") (pin "4") (pinfunction "GND_4") (pintype "passive"))
    )
    (net (code "49") (name "Net-(C10-Pad2)") (class "Default")
      (node (ref "C10") (pin "2") (pinfunction "2_2") (pintype "passive"))
      (node (ref "R5") (pin "1") (pinfunction "1_1") (pintype "passive"))
      (node (ref "R6") (pin "1") (pinfunction "1_1") (pintype "passive"))
      (node (ref "RET1") (pin "1") (pinfunction "1_1") (pintype "passive"))
    )
    (net (code "50") (name "Net-(D1-A)") (class "Default")
      (node (ref "D1") (pin "1") (pinfunction "A_1") (pintype "passive"))
      (node (ref "DC5V") (pin "1") (pinfunction "1_1") (pintype "passive"))
    )
    (net (code "51") (name "Net-(D2-K)") (class "Default")
      (node (ref "D2") (pin "2") (pinfunction "K_2") (pintype "passive"))
      (node (ref "R2") (pin "2") (pinfunction "2_2") (pintype "passive"))
    )
    (net (code "52") (name "Net-(D4-K)") (class "Default")
      (node (ref "D4") (pin "2") (pinfunction "K_2") (pintype "passive"))
      (node (ref "K1") (pin "3") (pinfunction "3_3") (pintype "passive"))
      (node (ref "Q4") (pin "3") (pinfunction "C_3") (pintype "passive"))
      (node (ref "R42") (pin "2") (pinfunction "2_2") (pintype "passive"))
    )
    (net (code "53") (name "Net-(D20-A)") (class "Default")
      (node (ref "D20") (pin "1") (pinfunction "A_1") (pintype "passive"))
      (node (ref "PR102") (pin "9") (pinfunction "9_9") (pintype "passive"))
    )
    (net (code "54") (name "Net-(D21-A)") (class "Default")
      (node (ref "D21") (pin "1") (pinfunction "A_1") (pintype "passive"))
      (node (ref "PR102") (pin "8") (pinfunction "8_8") (pintype "passive"))
    )
    (net (code "55") (name "Net-(D22-A)") (class "Default")
      (node (ref "D22") (pin "1") (pinfunction "A_1") (pintype "passive"))
      (node (ref "PR102") (pin "7") (pinfunction "7_7") (pintype "passive"))
    )
    (net (code "56") (name "Net-(D23-A)") (class "Default")
      (node (ref "D23") (pin "1") (pinfunction "A_1") (pintype "passive"))
      (node (ref "PR102") (pin "6") (pinfunction "6_6") (pintype "passive"))
    )
    (net (code "57") (name "Net-(D24-A)") (class "Default")
      (node (ref "D24") (pin "1") (pinfunction "A_1") (pintype "passive"))
      (node (ref "PR102") (pin "5") (pinfunction "5_5") (pintype "passive"))
    )
    (net (code "58") (name "Net-(D25-A)") (class "Default")
      (node (ref "D25") (pin "1") (pinfunction "A_1") (pintype "passive"))
      (node (ref "PR102") (pin "4") (pinfunction "4_4") (pintype "passive"))
    )
    (net (code "59") (name "Net-(D26-A)") (class "Default")
      (node (ref "D26") (pin "1") (pinfunction "A_1") (pintype "passive"))
      (node (ref "PR102") (pin "3") (pinfunction "3_3") (pintype "passive"))
    )
    (net (code "60") (name "Net-(D27-A)") (class "Default")
      (node (ref "D27") (pin "1") (pinfunction "A_1") (pintype "passive"))
      (node (ref "PR102") (pin "2") (pinfunction "2_2") (pintype "passive"))
    )
    (net (code "61") (name "Net-(D42-A)") (class "Default")
      (node (ref "D42") (pin "1") (pinfunction "A_1") (pintype "passive"))
      (node (ref "R42") (pin "1") (pinfunction "1_1") (pintype "passive"))
    )
    (net (code "62") (name "Net-(JLED-Pad2)") (class "Default")
      (node (ref "JLED") (pin "2") (pinfunction "2_2") (pintype "passive"))
      (node (ref "PR102") (pin "1") (pinfunction "1_1") (pintype "passive"))
    )
    (net (code "63") (name "Net-(JP3-Pad1)") (class "Default")
      (node (ref "JP3") (pin "1") (pinfunction "1_1") (pintype "passive"))
      (node (ref "K1") (pin "2") (pinfunction "2_2") (pintype "passive"))
    )
    (net (code "64") (name "Net-(JP3-Pad2)") (class "Default")
      (node (ref "JP3") (pin "2") (pinfunction "2_2") (pintype "passive"))
      (node (ref "K1") (pin "4") (pinfunction "4_4") (pintype "passive"))
    )
    (net (code "65") (name "Net-(JP3-Pad3)") (class "Default")
      (node (ref "JP3") (pin "3") (pinfunction "3_3") (pintype "passive"))
      (node (ref "K1") (pin "1") (pinfunction "1_1") (pintype "passive"))
    )
    (net (code "66") (name "Net-(Q1-B)") (class "Default")
      (node (ref "Q1") (pin "2") (pinfunction "B_2") (pintype "passive"))
      (node (ref "R5") (pin "2") (pinfunction "2_2") (pintype "passive"))
    )
    (net (code "67") (name "Net-(Q1-C)") (class "Default")
      (node (ref "Q1") (pin "3") (pinfunction "C_3") (pintype "passive"))
      (node (ref "Q3") (pin "2") (pinfunction "B_2") (pintype "passive"))
      (node (ref "R4") (pin "1") (pinfunction "1_1") (pintype "passive"))
    )
    (net (code "68") (name "Net-(Q2-B)") (class "Default")
      (node (ref "Q2") (pin "2") (pinfunction "B_2") (pintype "passive"))
      (node (ref "R21") (pin "2") (pinfunction "2_2") (pintype "passive"))
    )
    (net (code "69") (name "Net-(Q2-C)") (class "Default")
      (node (ref "Q2") (pin "3") (pinfunction "C_3") (pintype "passive"))
      (node (ref "SPK") (pin "1") (pinfunction "A_1") (pintype "passive"))
    )
    (net (code "70") (name "Net-(Q4-B)") (class "Default")
      (node (ref "Q4") (pin "2") (pinfunction "B_2") (pintype "passive"))
      (node (ref "R41") (pin "2") (pinfunction "2_2") (pintype "passive"))
    )
    (net (code "71") (name "Net-(Q5-B)") (class "Default")
      (node (ref "Q5") (pin "2") (pinfunction "B_2") (pintype "passive"))
      (node (ref "R8") (pin "1") (pinfunction "1_1") (pintype "passive"))
    )
    (net (code "72") (name "Net-(Q10-B)") (class "Default")
      (node (ref "Q10") (pin "2") (pinfunction "B_2") (pintype "passive"))
      (node (ref "R10") (pin "1") (pinfunction "1_1") (pintype "passive"))
    )
    (net (code "73") (name "Net-(Q10-C)") (class "Default")
      (node (ref "Q10") (pin "3") (pinfunction "C_3") (pintype "passive"))
      (node (ref "SMG1") (pin "12") (pinfunction "C4_12") (pintype "passive"))
    )
    (net (code "74") (name "Net-(Q10-E)") (class "Default")
      (node (ref "JSM") (pin "2") (pinfunction "2_2") (pintype "passive"))
      (node (ref "Q10") (pin "1") (pinfunction "E_1") (pintype "passive"))
      (node (ref "Q11") (pin "1") (pinfunction "E_1") (pintype "passive"))
      (node (ref "Q12") (pin "1") (pinfunction "E_1") (pintype "passive"))
      (node (ref "Q13") (pin "1") (pinfunction "E_1") (pintype "passive"))
    )
    (net (code "75") (name "Net-(Q11-B)") (class "Default")
      (node (ref "Q11") (pin "2") (pinfunction "B_2") (pintype "passive"))
      (node (ref "R11") (pin "1") (pinfunction "1_1") (pintype "passive"))
    )
    (net (code "76") (name "Net-(Q11-C)") (class "Default")
      (node (ref "Q11") (pin "3") (pinfunction "C_3") (pintype "passive"))
      (node (ref "SMG1") (pin "9") (pinfunction "C3_9") (pintype "passive"))
    )
    (net (code "77") (name "Net-(Q12-B)") (class "Default")
      (node (ref "Q12") (pin "2") (pinfunction "B_2") (pintype "passive"))
      (node (ref "R12") (pin "1") (pinfunction "1_1") (pintype "passive"))
    )
    (net (code "78") (name "Net-(Q12-C)") (class "Default")
      (node (ref "Q12") (pin "3") (pinfunction "C_3") (pintype "passive"))
      (node (ref "SMG1") (pin "8") (pinfunction "C2_8") (pintype "passive"))
    )
    (net (code "79") (name "Net-(Q13-B)") (class "Default")
      (node (ref "Q13") (pin "2") (pinfunction "B_2") (pintype "passive"))
      (node (ref "R13") (pin "1") (pinfunction "1_1") (pintype "passive"))
    )
    (net (code "80") (name "Net-(Q13-C)") (class "Default")
      (node (ref "Q13") (pin "3") (pinfunction "C_3") (pintype "passive"))
      (node (ref "SMG1") (pin "6") (pinfunction "C0_6") (pintype "passive"))
    )
    (net (code "81") (name "Net-(RW1-TAP)") (class "Default")
      (node (ref "P3") (pin "3") (pinfunction "3_3") (pintype "passive"))
      (node (ref "RW1") (pin "3") (pinfunction "TAP_3") (pintype "passive"))
    )
    (net (code "82") (name "Net-(SMG1-a)") (class "Default")
      (node (ref "R31") (pin "2") (pinfunction "2_2") (pintype "passive"))
      (node (ref "SMG1") (pin "11") (pinfunction "a_11") (pintype "passive"))
    )
    (net (code "83") (name "Net-(SMG1-b)") (class "Default")
      (node (ref "R32") (pin "2") (pinfunction "2_2") (pintype "passive"))
      (node (ref "SMG1") (pin "7") (pinfunction "b_7") (pintype "passive"))
    )
    (net (code "84") (name "Net-(SMG1-c)") (class "Default")
      (node (ref "R33") (pin "2") (pinfunction "2_2") (pintype "passive"))
      (node (ref "SMG1") (pin "4") (pinfunction "c_4") (pintype "passive"))
    )
    (net (code "85") (name "Net-(SMG1-d)") (class "Default")
      (node (ref "R34") (pin "2") (pinfunction "2_2") (pintype "passive"))
      (node (ref "SMG1") (pin "2") (pinfunction "d_2") (pintype "passive"))
    )
    (net (code "86") (name "Net-(SMG1-dp)") (class "Default")
      (node (ref "R38") (pin "2") (pinfunction "2_2") (pintype "passive"))
      (node (ref "SMG1") (pin "3") (pinfunction "dp_3") (pintype "passive"))
    )
    (net (code "87") (name "Net-(SMG1-e)") (class "Default")
      (node (ref "R35") (pin "2") (pinfunction "2_2") (pintype "passive"))
      (node (ref "SMG1") (pin "1") (pinfunction "e_1") (pintype "passive"))
    )
    (net (code "88") (name "Net-(SMG1-f)") (class "Default")
      (node (ref "R36") (pin "2") (pinfunction "2_2") (pintype "passive"))
      (node (ref "SMG1") (pin "10") (pinfunction "f_10") (pintype "passive"))
    )
    (net (code "89") (name "Net-(SMG1-g)") (class "Default")
      (node (ref "R37") (pin "2") (pinfunction "2_2") (pintype "passive"))
      (node (ref "SMG1") (pin "5") (pinfunction "g_5") (pintype "passive"))
    )
    (net (code "90") (name "Net-(STC89C52-XTAL1)") (class "Default")
      (node (ref "C2") (pin "2") (pinfunction "2_2") (pintype "passive"))
      (node (ref "STC89C52") (pin "19") (pinfunction "XTAL1_19") (pintype "passive"))
      (node (ref "Y0") (pin "1") (pinfunction "1_1") (pintype "passive"))
    )
    (net (code "91") (name "Net-(STC89C52-XTAL2)") (class "Default")
      (node (ref "C3") (pin "2") (pinfunction "2_2") (pintype "passive"))
      (node (ref "STC89C52") (pin "18") (pinfunction "XTAL2_18") (pintype "passive"))
      (node (ref "Y0") (pin "2") (pinfunction "2_2") (pintype "passive"))
    )
    (net (code "92") (name "Net-(U1-OUT)") (class "Default")
      (node (ref "R7") (pin "1") (pinfunction "1_1") (pintype "passive"))
      (node (ref "R8") (pin "2") (pinfunction "2_2") (pintype "passive"))
      (node (ref "U1") (pin "3") (pinfunction "OUT_3") (pintype "passive"))
    )
    (net (code "93") (name "Net-(U3-UD+)") (class "Default")
      (node (ref "U3") (pin "5") (pinfunction "UD+_5") (pintype "passive"))
      (node (ref "USB") (pin "3") (pinfunction "D+_3") (pintype "passive"))
    )
    (net (code "94") (name "Net-(U3-UD-)") (class "Default")
      (node (ref "U3") (pin "6") (pinfunction "UD-_6") (pintype "passive"))
      (node (ref "USB") (pin "2") (pinfunction "D-_2") (pintype "passive"))
    )
    (net (code "95") (name "Net-(U3-X0)") (class "Default")
      (node (ref "C9") (pin "1") (pinfunction "1_1") (pintype "passive"))
      (node (ref "U3") (pin "8") (pinfunction "X0_8") (pintype "passive"))
      (node (ref "Y1") (pin "2") (pinfunction "OSC2_2") (pintype "passive"))
    )
    (net (code "96") (name "Net-(U3-X1)") (class "Default")
      (node (ref "C8") (pin "1") (pinfunction "1_1") (pintype "passive"))
      (node (ref "U3") (pin "7") (pinfunction "X1_7") (pintype "passive"))
      (node (ref "Y1") (pin "1") (pinfunction "OSC1_1") (pintype "passive"))
    )
    (net (code "97") (name "VCC") (class "Default")
      (node (ref "C1") (pin "1") (pinfunction "1_1") (pintype "passive"))
      (node (ref "C10") (pin "1") (pinfunction "1_1") (pintype "passive"))
      (node (ref "C4") (pin "1") (pinfunction "1_1") (pintype "passive"))
      (node (ref "C5") (pin "1") (pinfunction "1_1") (pintype "passive"))
      (node (ref "C6") (pin "2") (pinfunction "2_2") (pintype "passive"))
      (node (ref "D1") (pin "2") (pinfunction "K_2") (pintype "passive"))
      (node (ref "D2") (pin "1") (pinfunction "A_1") (pintype "passive"))
      (node (ref "JLED") (pin "1") (pinfunction "1_1") (pintype "passive"))
      (node (ref "JPW") (pin "4") (pinfunction "4_4") (pintype "passive"))
      (node (ref "JPW") (pin "5") (pinfunction "5_5") (pintype "passive"))
      (node (ref "JPW") (pin "6") (pinfunction "6_6") (pintype "passive"))
      (node (ref "JSM") (pin "1") (pinfunction "1_1") (pintype "passive"))
      (node (ref "P3") (pin "15") (pinfunction "15_15") (pintype "passive"))
      (node (ref "P3") (pin "2") (pinfunction "2_2") (pintype "passive"))
      (node (ref "P4") (pin "3") (pinfunction "3_3") (pintype "passive"))
      (node (ref "P5") (pin "3") (pinfunction "3_3") (pintype "passive"))
      (node (ref "Q2") (pin "1") (pinfunction "E_1") (pintype "passive"))
      (node (ref "Q4") (pin "1") (pinfunction "E_1") (pintype "passive"))
      (node (ref "R4") (pin "2") (pinfunction "2_2") (pintype "passive"))
      (node (ref "R43") (pin "2") (pinfunction "2_2") (pintype "passive"))
      (node (ref "R44") (pin "2") (pinfunction "2_2") (pintype "passive"))
      (node (ref "R45") (pin "2") (pinfunction "2_2") (pintype "passive"))
      (node (ref "RET1") (pin "2") (pinfunction "2_2") (pintype "passive"))
      (node (ref "RW1") (pin "2") (pinfunction "B_2") (pintype "passive"))
      (node (ref "STC89C52") (pin "40") (pinfunction "VCC_40") (pintype "passive"))
      (node (ref "U2") (pin "8") (pinfunction "VCC_8") (pintype "passive"))
      (node (ref "U3") (pin "16") (pinfunction "VCC_16") (pintype "passive"))
      (node (ref "USB") (pin "1") (pinfunction "+5V_1") (pintype "passive"))
    )
    (net (code "98") (name "unconnected-(U3-R232-Pad15)") (class "Default")
      (node (ref "U3") (pin "15") (pinfunction "R232_15") (pintype "passive"))
    )
    (net (code "99") (name "unconnected-(U3-~{CTS}-Pad9)") (class "Default")
      (node (ref "U3") (pin "9") (pinfunction "~{CTS}_9") (pintype "passive"))
    )
    (net (code "100") (name "unconnected-(U3-~{DCD}-Pad12)") (class "Default")
      (node (ref "U3") (pin "12") (pinfunction "~{DCD}_12") (pintype "passive"))
    )
    (net (code "101") (name "unconnected-(U3-~{DSR}-Pad10)") (class "Default")
      (node (ref "U3") (pin "10") (pinfunction "~{DSR}_10") (pintype "passive"))
    )
    (net (code "102") (name "unconnected-(U3-~{DTR}-Pad13)") (class "Default")
      (node (ref "U3") (pin "13") (pinfunction "~{DTR}_13") (pintype "passive"))
    )
    (net (code "103") (name "unconnected-(U3-~{RI}-Pad11)") (class "Default")
      (node (ref "U3") (pin "11") (pinfunction "~{RI}_11") (pintype "passive"))
    )
    (net (code "104") (name "unconnected-(U3-~{RTS}-Pad14)") (class "Default")
      (node (ref "U3") (pin "14") (pinfunction "~{RTS}_14") (pintype "passive"))
    )
  )
)
